# receiver_-_Copy.net
KiCad netlist of a schematic drawn in EAGLE
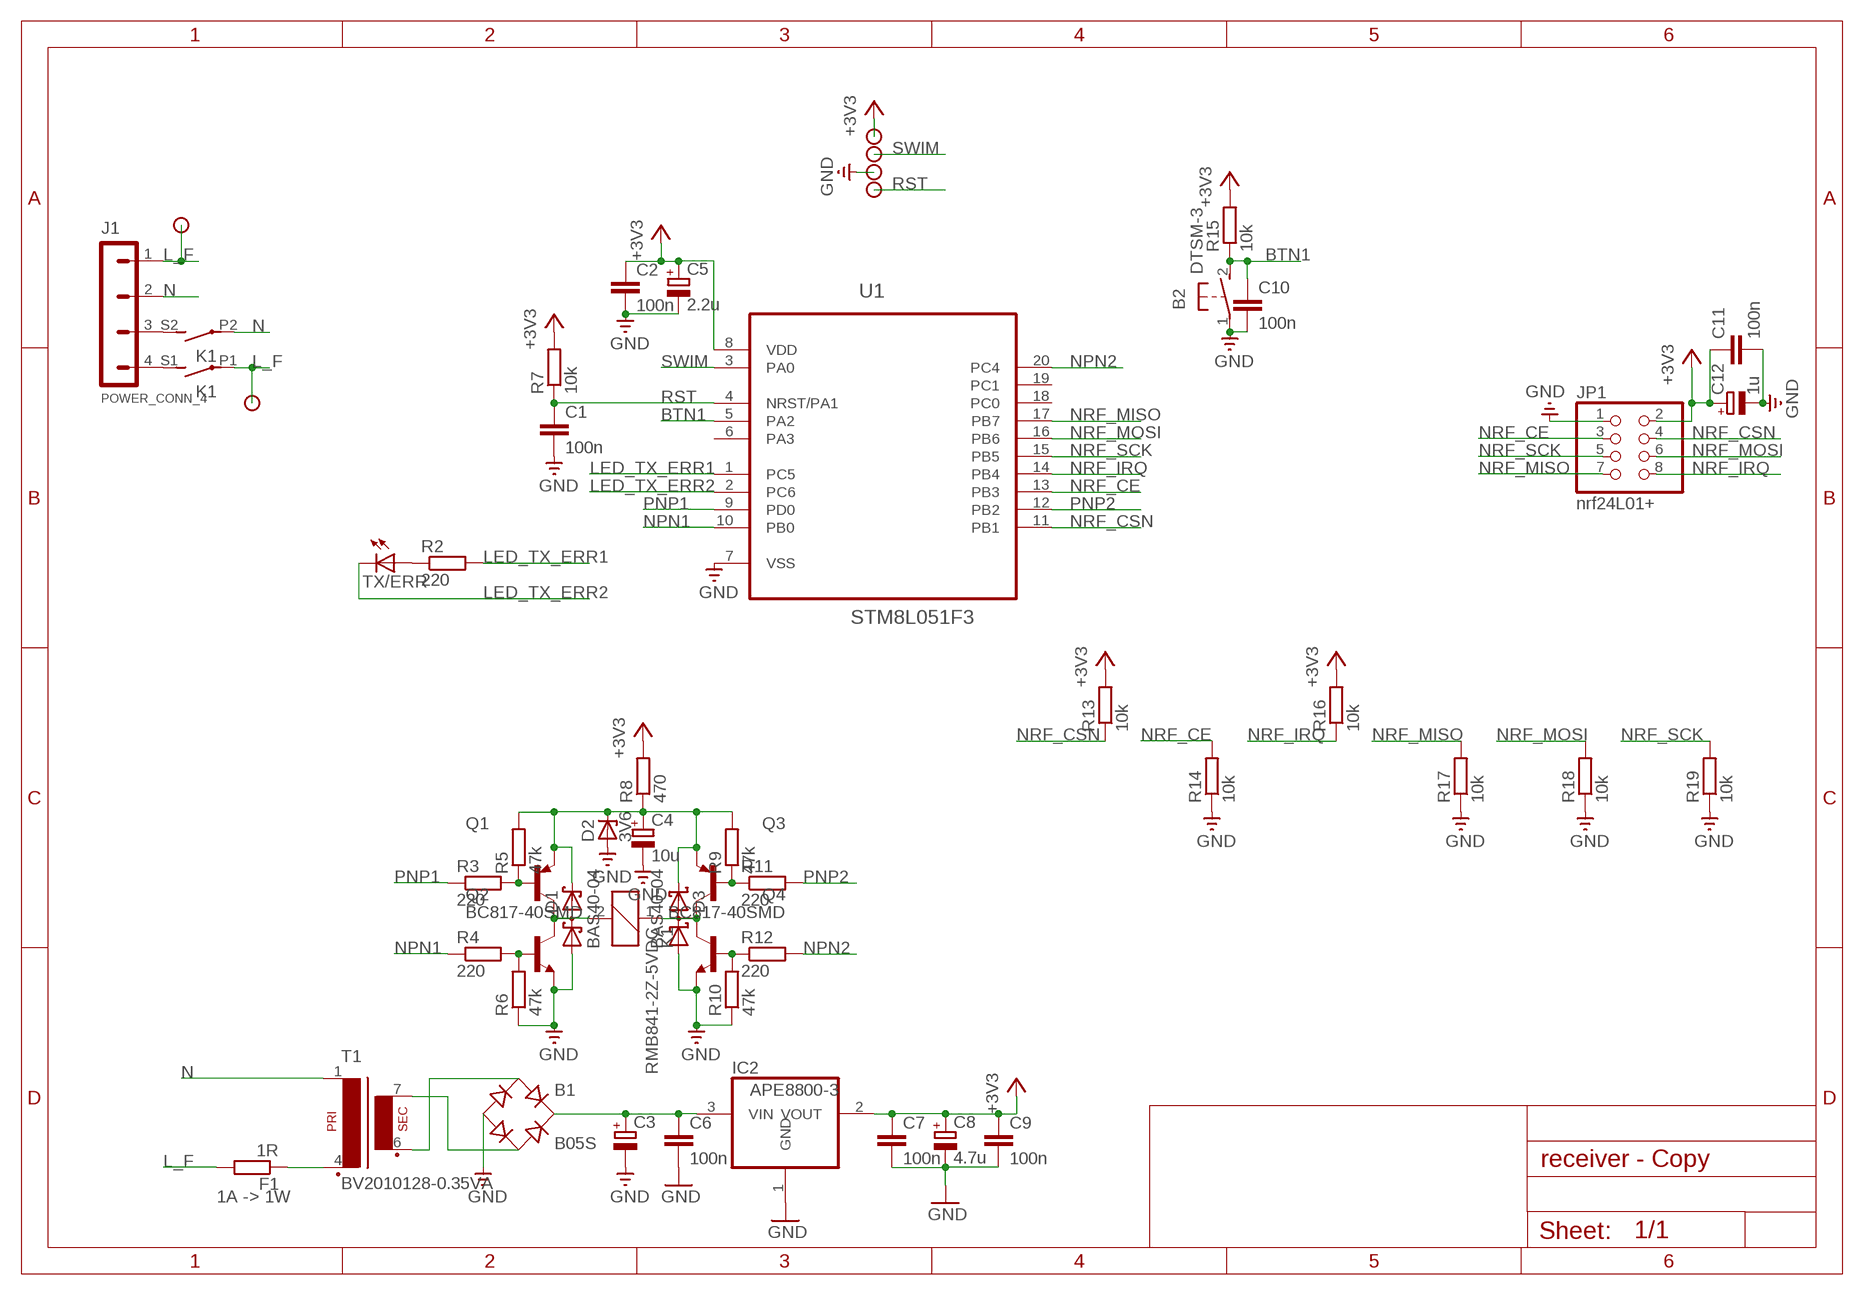
[diagram p0: schematic, sheet 1]

(export (version "E")
  (design (tool "Eeschema 10.0.6"))
  (components
    (comp (ref "B1")
      (value "B05S")
      (footprint "eagle-import:MBS")
      (libsource (lib "eagle-import") (part "BS05"))
    )
    (comp (ref "B2")
      (value "DTSM-3")
      (footprint "eagle-import:DTSM-3")
      (libsource (lib "eagle-import") (part "DTSM-3"))
    )
    (comp (ref "C1")
      (value "100n")
      (footprint "eagle-import:C0603K")
      (libsource (lib "eagle-import") (part "C-EUC0603K"))
    )
    (comp (ref "C2")
      (value "100n")
      (footprint "eagle-import:C0603K")
      (libsource (lib "eagle-import") (part "C-EUC0603K"))
    )
    (comp (ref "C3")
      (value "CPOL-EUSMCB")
      (footprint "eagle-import:SMC_B")
      (libsource (lib "eagle-import") (part "CPOL-EUSMCB"))
    )
    (comp (ref "C4")
      (value "10u")
      (footprint "eagle-import:SMC_B")
      (libsource (lib "eagle-import") (part "CPOL-EUSMCB"))
    )
    (comp (ref "C5")
      (value "2.2u")
      (footprint "eagle-import:SMC_A")
      (libsource (lib "eagle-import") (part "CPOL-EUSMCA"))
    )
    (comp (ref "C6")
      (value "100n")
      (footprint "eagle-import:C0603K")
      (libsource (lib "eagle-import") (part "C-EUC0603K"))
    )
    (comp (ref "C7")
      (value "100n")
      (footprint "eagle-import:C0603K")
      (libsource (lib "eagle-import") (part "C-EUC0603K"))
    )
    (comp (ref "C8")
      (value "4.7u")
      (footprint "eagle-import:SMC_A")
      (libsource (lib "eagle-import") (part "CPOL-EUSMCA"))
    )
    (comp (ref "C9")
      (value "100n")
      (footprint "eagle-import:C0603K")
      (libsource (lib "eagle-import") (part "C-EUC0603K"))
    )
    (comp (ref "C10")
      (value "100n")
      (footprint "eagle-import:C0603K")
      (libsource (lib "eagle-import") (part "C-EUC0603K"))
    )
    (comp (ref "C11")
      (value "100n")
      (footprint "eagle-import:C0603K")
      (libsource (lib "eagle-import") (part "C-EUC0603K"))
    )
    (comp (ref "C12")
      (value "1u")
      (footprint "eagle-import:SMC_A")
      (libsource (lib "eagle-import") (part "CPOL-EUSMCA"))
    )
    (comp (ref "D1")
      (value "BAS40-04")
      (footprint "eagle-import:SOT23")
      (libsource (lib "eagle-import") (part "BAS40-04"))
    )
    (comp (ref "D2")
      (value "3V6")
      (footprint "eagle-import:SOT23")
      (libsource (lib "eagle-import") (part "ZENER-DIODESOT23"))
    )
    (comp (ref "D3")
      (value "BAS40-04")
      (footprint "eagle-import:SOT23")
      (libsource (lib "eagle-import") (part "BAS40-04"))
    )
    (comp (ref "F1")
      (value "1R")
      (footprint "eagle-import:0207_10")
      (libsource (lib "eagle-import") (part "R-EU_0207/10"))
    )
    (comp (ref "IC2")
      (value "APE8800-3")
      (footprint "eagle-import:SOT23")
      (libsource (lib "eagle-import") (part "APE8800-3"))
    )
    (comp (ref "J1")
      (value "POWER_CONN_4")
      (footprint "eagle-import:TERMINAL_BLOCK_4")
      (libsource (lib "eagle-import") (part "POWER_CONN_4"))
    )
    (comp (ref "J2")
      (value "CON_PAD_THICK_WIRE")
      (footprint "eagle-import:SMD_PAD_THICK_WIRE")
      (libsource (lib "eagle-import") (part "CON_PAD_THICK_WIRE"))
    )
    (comp (ref "J3")
      (value "CON_PAD_THICK_WIRE")
      (footprint "eagle-import:SMD_PAD_THICK_WIRE")
      (libsource (lib "eagle-import") (part "CON_PAD_THICK_WIRE"))
    )
    (comp (ref "JP1")
      (value "nrf24L01+")
      (footprint "eagle-import:2X04")
      (libsource (lib "eagle-import") (part "PINHD-2X4"))
    )
    (comp (ref "K1")
      (value "RMB841-2Z-5VDC")
      (footprint "eagle-import:RMB841-2Z-5VDC")
      (libsource (lib "eagle-import") (part "RMB841-2Z-5VDC"))
    )
    (comp (ref "Q1")
      (value "BC807-40-PNP-SOT23-BEC")
      (footprint "eagle-import:SOT23-BEC")
      (libsource (lib "eagle-import") (part "-PNP-SOT23-BECBC807-40"))
    )
    (comp (ref "Q2")
      (value "BC817-40SMD")
      (footprint "eagle-import:SOT23-BEC")
      (libsource (lib "eagle-import") (part "BC817SMD-40"))
    )
    (comp (ref "Q3")
      (value "BC807-40-PNP-SOT23-BEC")
      (footprint "eagle-import:SOT23-BEC")
      (libsource (lib "eagle-import") (part "-PNP-SOT23-BECBC807-40"))
    )
    (comp (ref "Q4")
      (value "BC817-40SMD")
      (footprint "eagle-import:SOT23-BEC")
      (libsource (lib "eagle-import") (part "BC817SMD-40"))
    )
    (comp (ref "R2")
      (value "220")
      (footprint "eagle-import:R0603")
      (libsource (lib "eagle-import") (part "R-EU_R0603"))
    )
    (comp (ref "R3")
      (value "220")
      (footprint "eagle-import:R0603")
      (libsource (lib "eagle-import") (part "R-EU_R0603"))
    )
    (comp (ref "R4")
      (value "220")
      (footprint "eagle-import:R0603")
      (libsource (lib "eagle-import") (part "R-EU_R0603"))
    )
    (comp (ref "R5")
      (value "47k")
      (footprint "eagle-import:R0603")
      (libsource (lib "eagle-import") (part "R-EU_R0603"))
    )
    (comp (ref "R6")
      (value "47k")
      (footprint "eagle-import:R0603")
      (libsource (lib "eagle-import") (part "R-EU_R0603"))
    )
    (comp (ref "R7")
      (value "10k")
      (footprint "eagle-import:R0603")
      (libsource (lib "eagle-import") (part "R-EU_R0603"))
    )
    (comp (ref "R8")
      (value "470")
      (footprint "eagle-import:R0603")
      (libsource (lib "eagle-import") (part "R-EU_R0603"))
    )
    (comp (ref "R9")
      (value "47k")
      (footprint "eagle-import:R0603")
      (libsource (lib "eagle-import") (part "R-EU_R0603"))
    )
    (comp (ref "R10")
      (value "47k")
      (footprint "eagle-import:R0603")
      (libsource (lib "eagle-import") (part "R-EU_R0603"))
    )
    (comp (ref "R11")
      (value "220")
      (footprint "eagle-import:R0603")
      (libsource (lib "eagle-import") (part "R-EU_R0603"))
    )
    (comp (ref "R12")
      (value "220")
      (footprint "eagle-import:R0603")
      (libsource (lib "eagle-import") (part "R-EU_R0603"))
    )
    (comp (ref "R13")
      (value "10k")
      (footprint "eagle-import:R0603")
      (libsource (lib "eagle-import") (part "R-EU_R0603"))
    )
    (comp (ref "R14")
      (value "10k")
      (footprint "eagle-import:R0603")
      (libsource (lib "eagle-import") (part "R-EU_R0603"))
    )
    (comp (ref "R15")
      (value "10k")
      (footprint "eagle-import:R0603")
      (libsource (lib "eagle-import") (part "R-EU_R0603"))
    )
    (comp (ref "R16")
      (value "10k")
      (footprint "eagle-import:R0603")
      (libsource (lib "eagle-import") (part "R-EU_R0603"))
    )
    (comp (ref "R17")
      (value "10k")
      (footprint "eagle-import:R0603")
      (libsource (lib "eagle-import") (part "R-EU_R0603"))
    )
    (comp (ref "R18")
      (value "10k")
      (footprint "eagle-import:R0603")
      (libsource (lib "eagle-import") (part "R-EU_R0603"))
    )
    (comp (ref "R19")
      (value "10k")
      (footprint "eagle-import:R0603")
      (libsource (lib "eagle-import") (part "R-EU_R0603"))
    )
    (comp (ref "SIG_+3V1")
      (value "CON_PAD")
      (footprint "eagle-import:SMD_PAD")
      (libsource (lib "eagle-import") (part "CON_PAD"))
    )
    (comp (ref "SIG_GND")
      (value "CON_PAD")
      (footprint "eagle-import:SMD_PAD")
      (libsource (lib "eagle-import") (part "CON_PAD"))
    )
    (comp (ref "SIG_RST")
      (value "CON_PAD")
      (footprint "eagle-import:SMD_PAD")
      (libsource (lib "eagle-import") (part "CON_PAD"))
    )
    (comp (ref "SIG_SWIM")
      (value "CON_PAD")
      (footprint "eagle-import:SMD_PAD")
      (libsource (lib "eagle-import") (part "CON_PAD"))
    )
    (comp (ref "T1")
      (value "BV2010128-0.35VA")
      (footprint "eagle-import:BV2010128-0.35VA")
      (libsource (lib "eagle-import") (part "BV2010128-0.35VA"))
    )
    (comp (ref "TX/ERR")
      (value "LED3MM")
      (footprint "eagle-import:LED3MM")
      (libsource (lib "eagle-import") (part "LED3MM"))
    )
    (comp (ref "U1")
      (value "STM8L051F3")
      (footprint "eagle-import:TSSOP20")
      (libsource (lib "eagle-import") (part "STM8L051F3"))
    )
  )
  (nets
    (net (code "1") (name "+3V3") (class "Default")
      (node (ref "C11") (pin "1") (pinfunction "1_1") (pintype "passive"))
      (node (ref "C12") (pin "+") (pinfunction "+_+") (pintype "passive"))
      (node (ref "C2") (pin "1") (pinfunction "1_1") (pintype "passive"))
      (node (ref "C5") (pin "+") (pinfunction "+_+") (pintype "passive"))
      (node (ref "C7") (pin "1") (pinfunction "1_1") (pintype "passive"))
      (node (ref "C8") (pin "+") (pinfunction "+_+") (pintype "passive"))
      (node (ref "C9") (pin "1") (pinfunction "1_1") (pintype "passive"))
      (node (ref "IC2") (pin "2") (pinfunction "VOUT_2") (pintype "output"))
      (node (ref "JP1") (pin "2") (pinfunction "2_2") (pintype "passive"))
      (node (ref "R13") (pin "2") (pinfunction "2_2") (pintype "passive"))
      (node (ref "R15") (pin "2") (pinfunction "2_2") (pintype "passive"))
      (node (ref "R16") (pin "2") (pinfunction "2_2") (pintype "passive"))
      (node (ref "R7") (pin "2") (pinfunction "2_2") (pintype "passive"))
      (node (ref "R8") (pin "2") (pinfunction "2_2") (pintype "passive"))
      (node (ref "SIG_+3V1") (pin "P$1") (pinfunction "P$1_P$1") (pintype "bidirectional"))
      (node (ref "U1") (pin "8") (pinfunction "VDD_8") (pintype "power_in"))
    )
    (net (code "2") (name "/BTN1") (class "Default")
      (node (ref "B2") (pin "2") (pinfunction "2_2") (pintype "passive"))
      (node (ref "C10") (pin "1") (pinfunction "1_1") (pintype "passive"))
      (node (ref "R15") (pin "1") (pinfunction "1_1") (pintype "passive"))
      (node (ref "U1") (pin "5") (pinfunction "PA2_5") (pintype "bidirectional"))
    )
    (net (code "3") (name "/LED_TX_ERR1") (class "Default")
      (node (ref "R2") (pin "2") (pinfunction "2_2") (pintype "passive"))
      (node (ref "U1") (pin "1") (pinfunction "PC5_1") (pintype "bidirectional"))
    )
    (net (code "4") (name "/LED_TX_ERR2") (class "Default")
      (node (ref "TX/ERR") (pin "K") (pinfunction "C_K") (pintype "passive"))
      (node (ref "U1") (pin "2") (pinfunction "PC6_2") (pintype "bidirectional"))
    )
    (net (code "5") (name "/L_F") (class "Default")
      (node (ref "F1") (pin "2") (pinfunction "2_2") (pintype "passive"))
      (node (ref "J1") (pin "1") (pinfunction "P$1_1") (pintype "bidirectional"))
      (node (ref "J2") (pin "P$1") (pinfunction "P$1_P$1") (pintype "bidirectional"))
      (node (ref "J3") (pin "P$1") (pinfunction "P$1_P$1") (pintype "bidirectional"))
      (node (ref "K1") (pin "P1") (pinfunction "P_P1") (pintype "passive"))
    )
    (net (code "6") (name "/N") (class "Default")
      (node (ref "J1") (pin "2") (pinfunction "P$2_2") (pintype "bidirectional"))
      (node (ref "K1") (pin "P2") (pinfunction "P_P2") (pintype "passive"))
      (node (ref "T1") (pin "1") (pinfunction "P1_1") (pintype "passive"))
    )
    (net (code "7") (name "/NPN1") (class "Default")
      (node (ref "R4") (pin "1") (pinfunction "1_1") (pintype "passive"))
      (node (ref "U1") (pin "10") (pinfunction "PB0_10") (pintype "bidirectional"))
    )
    (net (code "8") (name "/NPN2") (class "Default")
      (node (ref "R12") (pin "2") (pinfunction "2_2") (pintype "passive"))
      (node (ref "U1") (pin "20") (pinfunction "PC4_20") (pintype "bidirectional"))
    )
    (net (code "9") (name "/NRF_CE") (class "Default")
      (node (ref "JP1") (pin "3") (pinfunction "3_3") (pintype "passive"))
      (node (ref "R14") (pin "2") (pinfunction "2_2") (pintype "passive"))
      (node (ref "U1") (pin "13") (pinfunction "PB3_13") (pintype "bidirectional"))
    )
    (net (code "10") (name "/NRF_CSN") (class "Default")
      (node (ref "JP1") (pin "4") (pinfunction "4_4") (pintype "passive"))
      (node (ref "R13") (pin "1") (pinfunction "1_1") (pintype "passive"))
      (node (ref "U1") (pin "11") (pinfunction "PB1_11") (pintype "bidirectional"))
    )
    (net (code "11") (name "/NRF_IRQ") (class "Default")
      (node (ref "JP1") (pin "8") (pinfunction "8_8") (pintype "passive"))
      (node (ref "R16") (pin "1") (pinfunction "1_1") (pintype "passive"))
      (node (ref "U1") (pin "14") (pinfunction "PB4_14") (pintype "bidirectional"))
    )
    (net (code "12") (name "/NRF_MISO") (class "Default")
      (node (ref "JP1") (pin "7") (pinfunction "7_7") (pintype "passive"))
      (node (ref "R17") (pin "2") (pinfunction "2_2") (pintype "passive"))
      (node (ref "U1") (pin "17") (pinfunction "PB7_17") (pintype "bidirectional"))
    )
    (net (code "13") (name "/NRF_MOSI") (class "Default")
      (node (ref "JP1") (pin "6") (pinfunction "6_6") (pintype "passive"))
      (node (ref "R18") (pin "2") (pinfunction "2_2") (pintype "passive"))
      (node (ref "U1") (pin "16") (pinfunction "PB6_16") (pintype "bidirectional"))
    )
    (net (code "14") (name "/NRF_SCK") (class "Default")
      (node (ref "JP1") (pin "5") (pinfunction "5_5") (pintype "passive"))
      (node (ref "R19") (pin "2") (pinfunction "2_2") (pintype "passive"))
      (node (ref "U1") (pin "15") (pinfunction "PB5_15") (pintype "bidirectional"))
    )
    (net (code "15") (name "/PNP1") (class "Default")
      (node (ref "R3") (pin "1") (pinfunction "1_1") (pintype "passive"))
      (node (ref "U1") (pin "9") (pinfunction "PD0_9") (pintype "bidirectional"))
    )
    (net (code "16") (name "/PNP2") (class "Default")
      (node (ref "R11") (pin "2") (pinfunction "2_2") (pintype "passive"))
      (node (ref "U1") (pin "12") (pinfunction "PB2_12") (pintype "bidirectional"))
    )
    (net (code "17") (name "/RST") (class "Default")
      (node (ref "C1") (pin "1") (pinfunction "1_1") (pintype "passive"))
      (node (ref "R7") (pin "1") (pinfunction "1_1") (pintype "passive"))
      (node (ref "SIG_RST") (pin "P$1") (pinfunction "P$1_P$1") (pintype "bidirectional"))
      (node (ref "U1") (pin "4") (pinfunction "NRST/PA1_4") (pintype "bidirectional"))
    )
    (net (code "18") (name "/SWIM") (class "Default")
      (node (ref "SIG_SWIM") (pin "P$1") (pinfunction "P$1_P$1") (pintype "bidirectional"))
      (node (ref "U1") (pin "3") (pinfunction "PA0_3") (pintype "power_in"))
    )
    (net (code "19") (name "GND") (class "Default")
      (node (ref "B1") (pin "-") (pinfunction "-_-") (pintype "passive"))
      (node (ref "B2") (pin "1") (pinfunction "1_1") (pintype "passive"))
      (node (ref "C1") (pin "2") (pinfunction "2_2") (pintype "passive"))
      (node (ref "C10") (pin "2") (pinfunction "2_2") (pintype "passive"))
      (node (ref "C11") (pin "2") (pinfunction "2_2") (pintype "passive"))
      (node (ref "C12") (pin "-") (pinfunction "-_-") (pintype "passive"))
      (node (ref "C2") (pin "2") (pinfunction "2_2") (pintype "passive"))
      (node (ref "C3") (pin "-") (pinfunction "-_-") (pintype "passive"))
      (node (ref "C4") (pin "-") (pinfunction "-_-") (pintype "passive"))
      (node (ref "C5") (pin "-") (pinfunction "-_-") (pintype "passive"))
      (node (ref "C6") (pin "2") (pinfunction "2_2") (pintype "passive"))
      (node (ref "C7") (pin "2") (pinfunction "2_2") (pintype "passive"))
      (node (ref "C8") (pin "-") (pinfunction "-_-") (pintype "passive"))
      (node (ref "C9") (pin "2") (pinfunction "2_2") (pintype "passive"))
      (node (ref "D1") (pin "1") (pinfunction "A1_1") (pintype "passive"))
      (node (ref "D2") (pin "1") (pinfunction "A_1") (pintype "passive"))
      (node (ref "D3") (pin "1") (pinfunction "A1_1") (pintype "passive"))
      (node (ref "IC2") (pin "1") (pinfunction "GND_1") (pintype "power_in"))
      (node (ref "JP1") (pin "1") (pinfunction "1_1") (pintype "passive"))
      (node (ref "Q2") (pin "E") (pinfunction "E_E") (pintype "passive"))
      (node (ref "Q4") (pin "E") (pinfunction "E_E") (pintype "passive"))
      (node (ref "R10") (pin "1") (pinfunction "1_1") (pintype "passive"))
      (node (ref "R14") (pin "1") (pinfunction "1_1") (pintype "passive"))
      (node (ref "R17") (pin "1") (pinfunction "1_1") (pintype "passive"))
      (node (ref "R18") (pin "1") (pinfunction "1_1") (pintype "passive"))
      (node (ref "R19") (pin "1") (pinfunction "1_1") (pintype "passive"))
      (node (ref "R6") (pin "1") (pinfunction "1_1") (pintype "passive"))
      (node (ref "SIG_GND") (pin "P$1") (pinfunction "P$1_P$1") (pintype "bidirectional"))
      (node (ref "U1") (pin "7") (pinfunction "VSS_7") (pintype "power_in"))
    )
    (net (code "20") (name "Net-(D1-C1A2)") (class "Default")
      (node (ref "D1") (pin "3") (pinfunction "C1A2_3") (pintype "passive"))
      (node (ref "K1") (pin "2") (pinfunction "2_2") (pintype "passive"))
      (node (ref "Q1") (pin "C") (pinfunction "C_C") (pintype "passive"))
      (node (ref "Q2") (pin "C") (pinfunction "C_C") (pintype "passive"))
    )
    (net (code "21") (name "Net-(D1-C2)") (class "Default")
      (node (ref "C4") (pin "+") (pinfunction "+_+") (pintype "passive"))
      (node (ref "D1") (pin "2") (pinfunction "C2_2") (pintype "passive"))
      (node (ref "D2") (pin "3") (pinfunction "C_3") (pintype "passive"))
      (node (ref "D3") (pin "2") (pinfunction "C2_2") (pintype "passive"))
      (node (ref "Q1") (pin "E") (pinfunction "E_E") (pintype "passive"))
      (node (ref "Q3") (pin "E") (pinfunction "E_E") (pintype "passive"))
      (node (ref "R5") (pin "2") (pinfunction "2_2") (pintype "passive"))
      (node (ref "R8") (pin "1") (pinfunction "1_1") (pintype "passive"))
      (node (ref "R9") (pin "2") (pinfunction "2_2") (pintype "passive"))
    )
    (net (code "22") (name "Net-(D3-C1A2)") (class "Default")
      (node (ref "D3") (pin "3") (pinfunction "C1A2_3") (pintype "passive"))
      (node (ref "K1") (pin "1") (pinfunction "1_1") (pintype "passive"))
      (node (ref "Q3") (pin "C") (pinfunction "C_C") (pintype "passive"))
      (node (ref "Q4") (pin "C") (pinfunction "C_C") (pintype "passive"))
    )
    (net (code "23") (name "Net-(IC2-VIN)") (class "Default")
      (node (ref "B1") (pin "+") (pinfunction "+_+") (pintype "passive"))
      (node (ref "C3") (pin "+") (pinfunction "+_+") (pintype "passive"))
      (node (ref "C6") (pin "1") (pinfunction "1_1") (pintype "passive"))
      (node (ref "IC2") (pin "3") (pinfunction "VIN_3") (pintype "input"))
    )
    (net (code "24") (name "Net-(J1-P$3)") (class "Default")
      (node (ref "J1") (pin "3") (pinfunction "P$3_3") (pintype "bidirectional"))
      (node (ref "K1") (pin "S2") (pinfunction "S_S2") (pintype "passive"))
    )
    (net (code "25") (name "Net-(J1-P$4)") (class "Default")
      (node (ref "J1") (pin "4") (pinfunction "P$4_4") (pintype "bidirectional"))
      (node (ref "K1") (pin "S1") (pinfunction "S_S1") (pintype "passive"))
    )
    (net (code "26") (name "Net-(Q1-PadB)") (class "Default")
      (node (ref "Q1") (pin "B") (pinfunction "B_B") (pintype "passive"))
      (node (ref "R3") (pin "2") (pinfunction "2_2") (pintype "passive"))
      (node (ref "R5") (pin "1") (pinfunction "1_1") (pintype "passive"))
    )
    (net (code "27") (name "Net-(Q2-PadB)") (class "Default")
      (node (ref "Q2") (pin "B") (pinfunction "B_B") (pintype "passive"))
      (node (ref "R4") (pin "2") (pinfunction "2_2") (pintype "passive"))
      (node (ref "R6") (pin "2") (pinfunction "2_2") (pintype "passive"))
    )
    (net (code "28") (name "Net-(Q3-PadB)") (class "Default")
      (node (ref "Q3") (pin "B") (pinfunction "B_B") (pintype "passive"))
      (node (ref "R11") (pin "1") (pinfunction "1_1") (pintype "passive"))
      (node (ref "R9") (pin "1") (pinfunction "1_1") (pintype "passive"))
    )
    (net (code "29") (name "Net-(Q4-PadB)") (class "Default")
      (node (ref "Q4") (pin "B") (pinfunction "B_B") (pintype "passive"))
      (node (ref "R10") (pin "2") (pinfunction "2_2") (pintype "passive"))
      (node (ref "R12") (pin "1") (pinfunction "1_1") (pintype "passive"))
    )
    (net (code "30") (name "Net-(R2-Pad1)") (class "Default")
      (node (ref "R2") (pin "1") (pinfunction "1_1") (pintype "passive"))
      (node (ref "TX/ERR") (pin "A") (pinfunction "A_A") (pintype "passive"))
    )
    (net (code "31") (name "Net-(T1-P2)") (class "Default")
      (node (ref "F1") (pin "1") (pinfunction "1_1") (pintype "passive"))
      (node (ref "T1") (pin "4") (pinfunction "P2_4") (pintype "passive"))
    )
    (net (code "32") (name "Net-(T1-S3)") (class "Default")
      (node (ref "B1") (pin "AC1") (pinfunction "AC1_AC1") (pintype "passive"))
      (node (ref "T1") (pin "6") (pinfunction "S3_6") (pintype "passive"))
    )
    (net (code "33") (name "Net-(T1-S4)") (class "Default")
      (node (ref "B1") (pin "AC2") (pinfunction "AC2_AC2") (pintype "passive"))
      (node (ref "T1") (pin "7") (pinfunction "S4_7") (pintype "passive"))
    )
    (net (code "34") (name "unconnected-(U1-PA3-Pad6)") (class "Default")
      (node (ref "U1") (pin "6") (pinfunction "PA3_6") (pintype "bidirectional"))
    )
    (net (code "35") (name "unconnected-(U1-PC0-Pad18)") (class "Default")
      (node (ref "U1") (pin "18") (pinfunction "PC0_18") (pintype "bidirectional"))
    )
    (net (code "36") (name "unconnected-(U1-PC1-Pad19)") (class "Default")
      (node (ref "U1") (pin "19") (pinfunction "PC1_19") (pintype "bidirectional"))
    )
  )
)
